# warps_v30.net
KiCad netlist of a schematic drawn in EAGLE
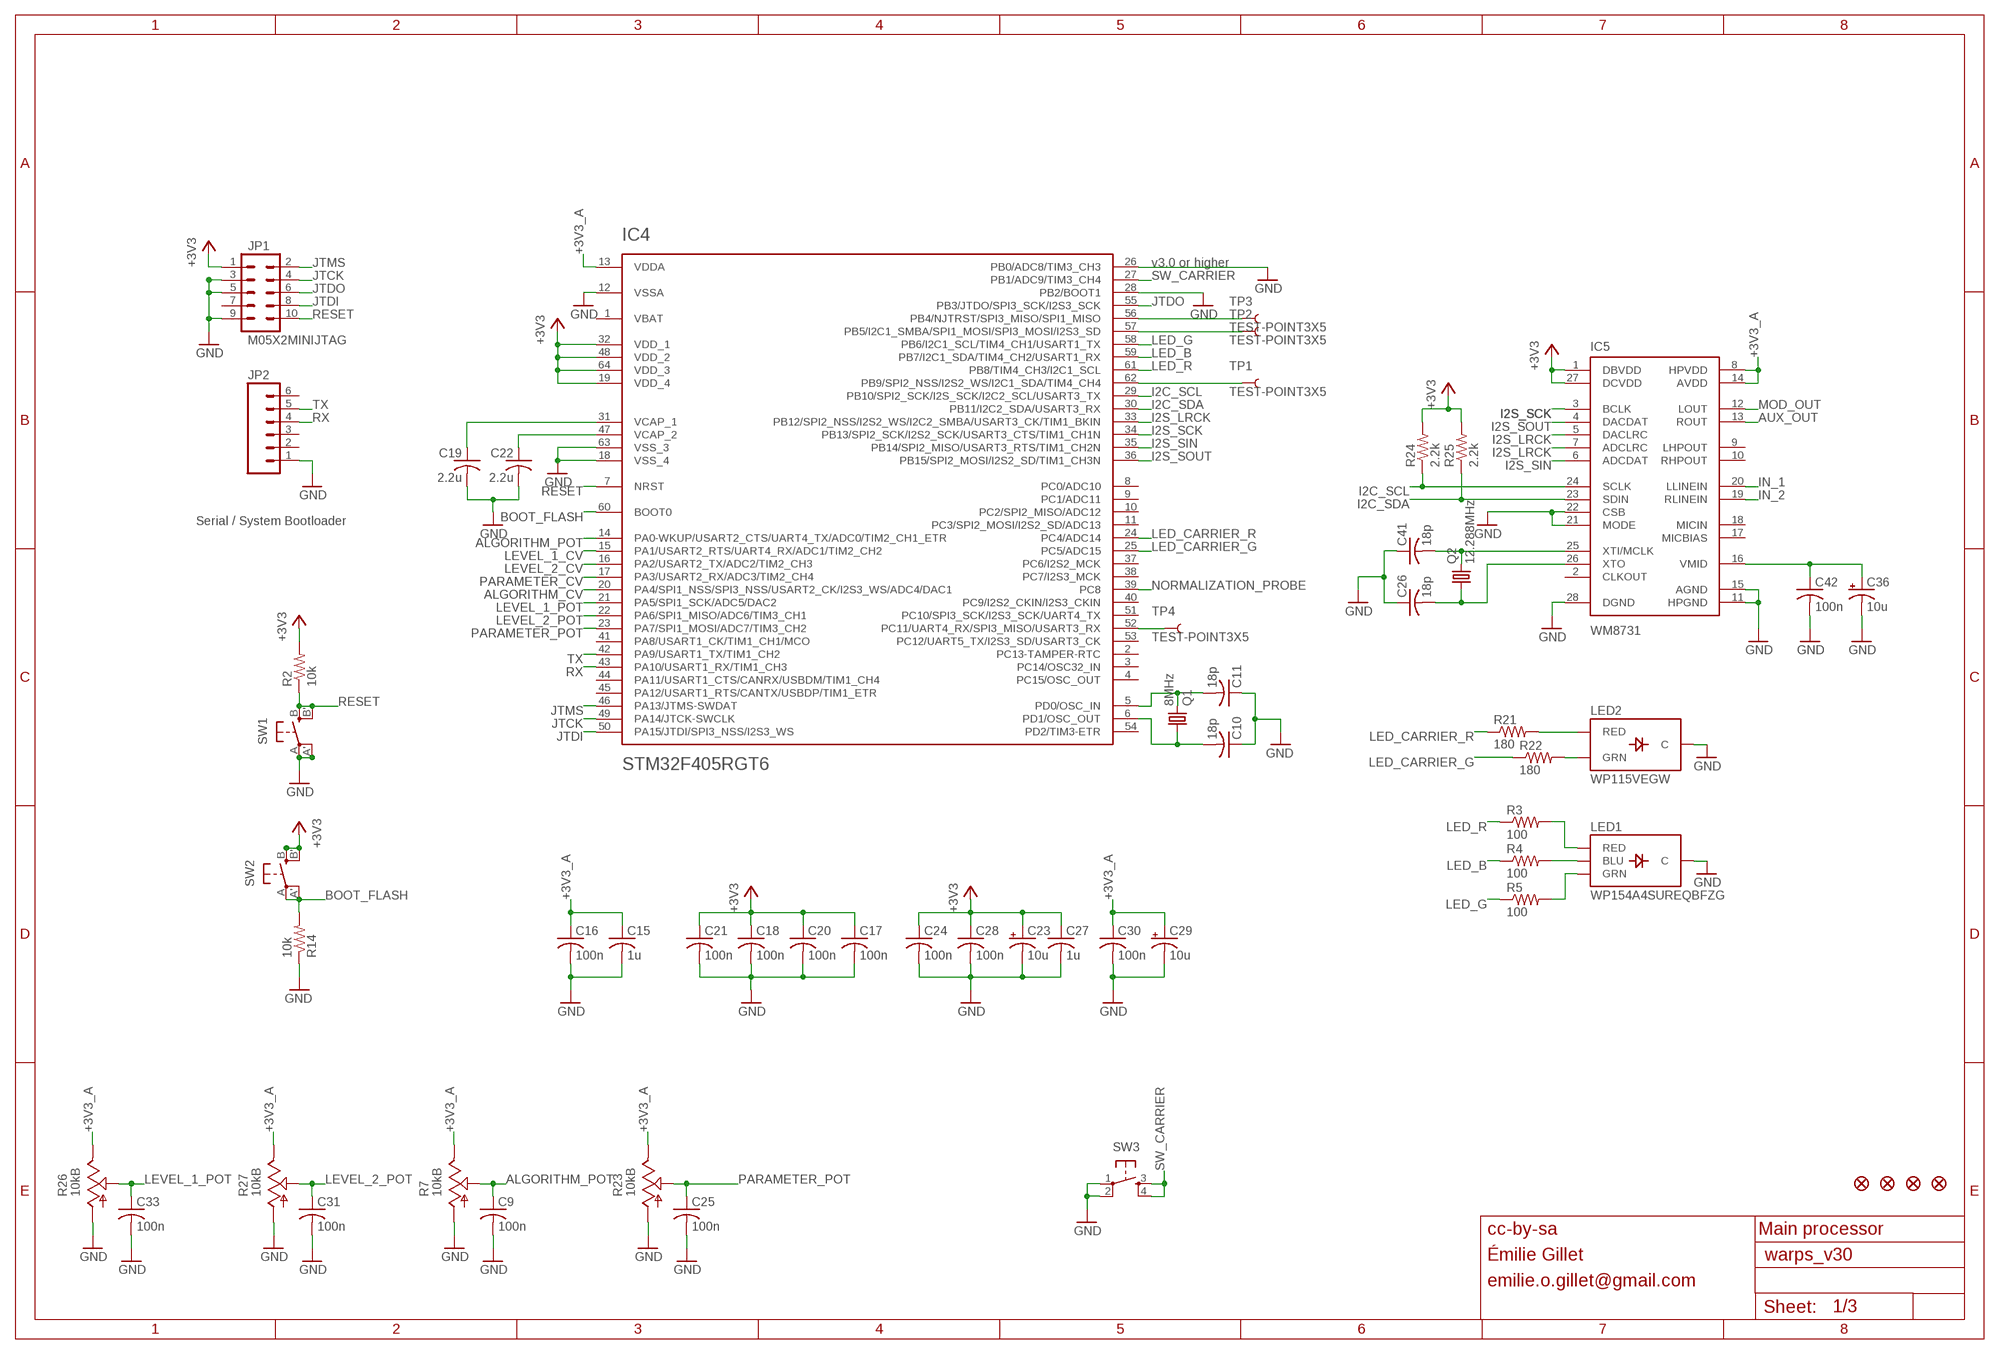
[diagram p0: schematic, sheet 1]
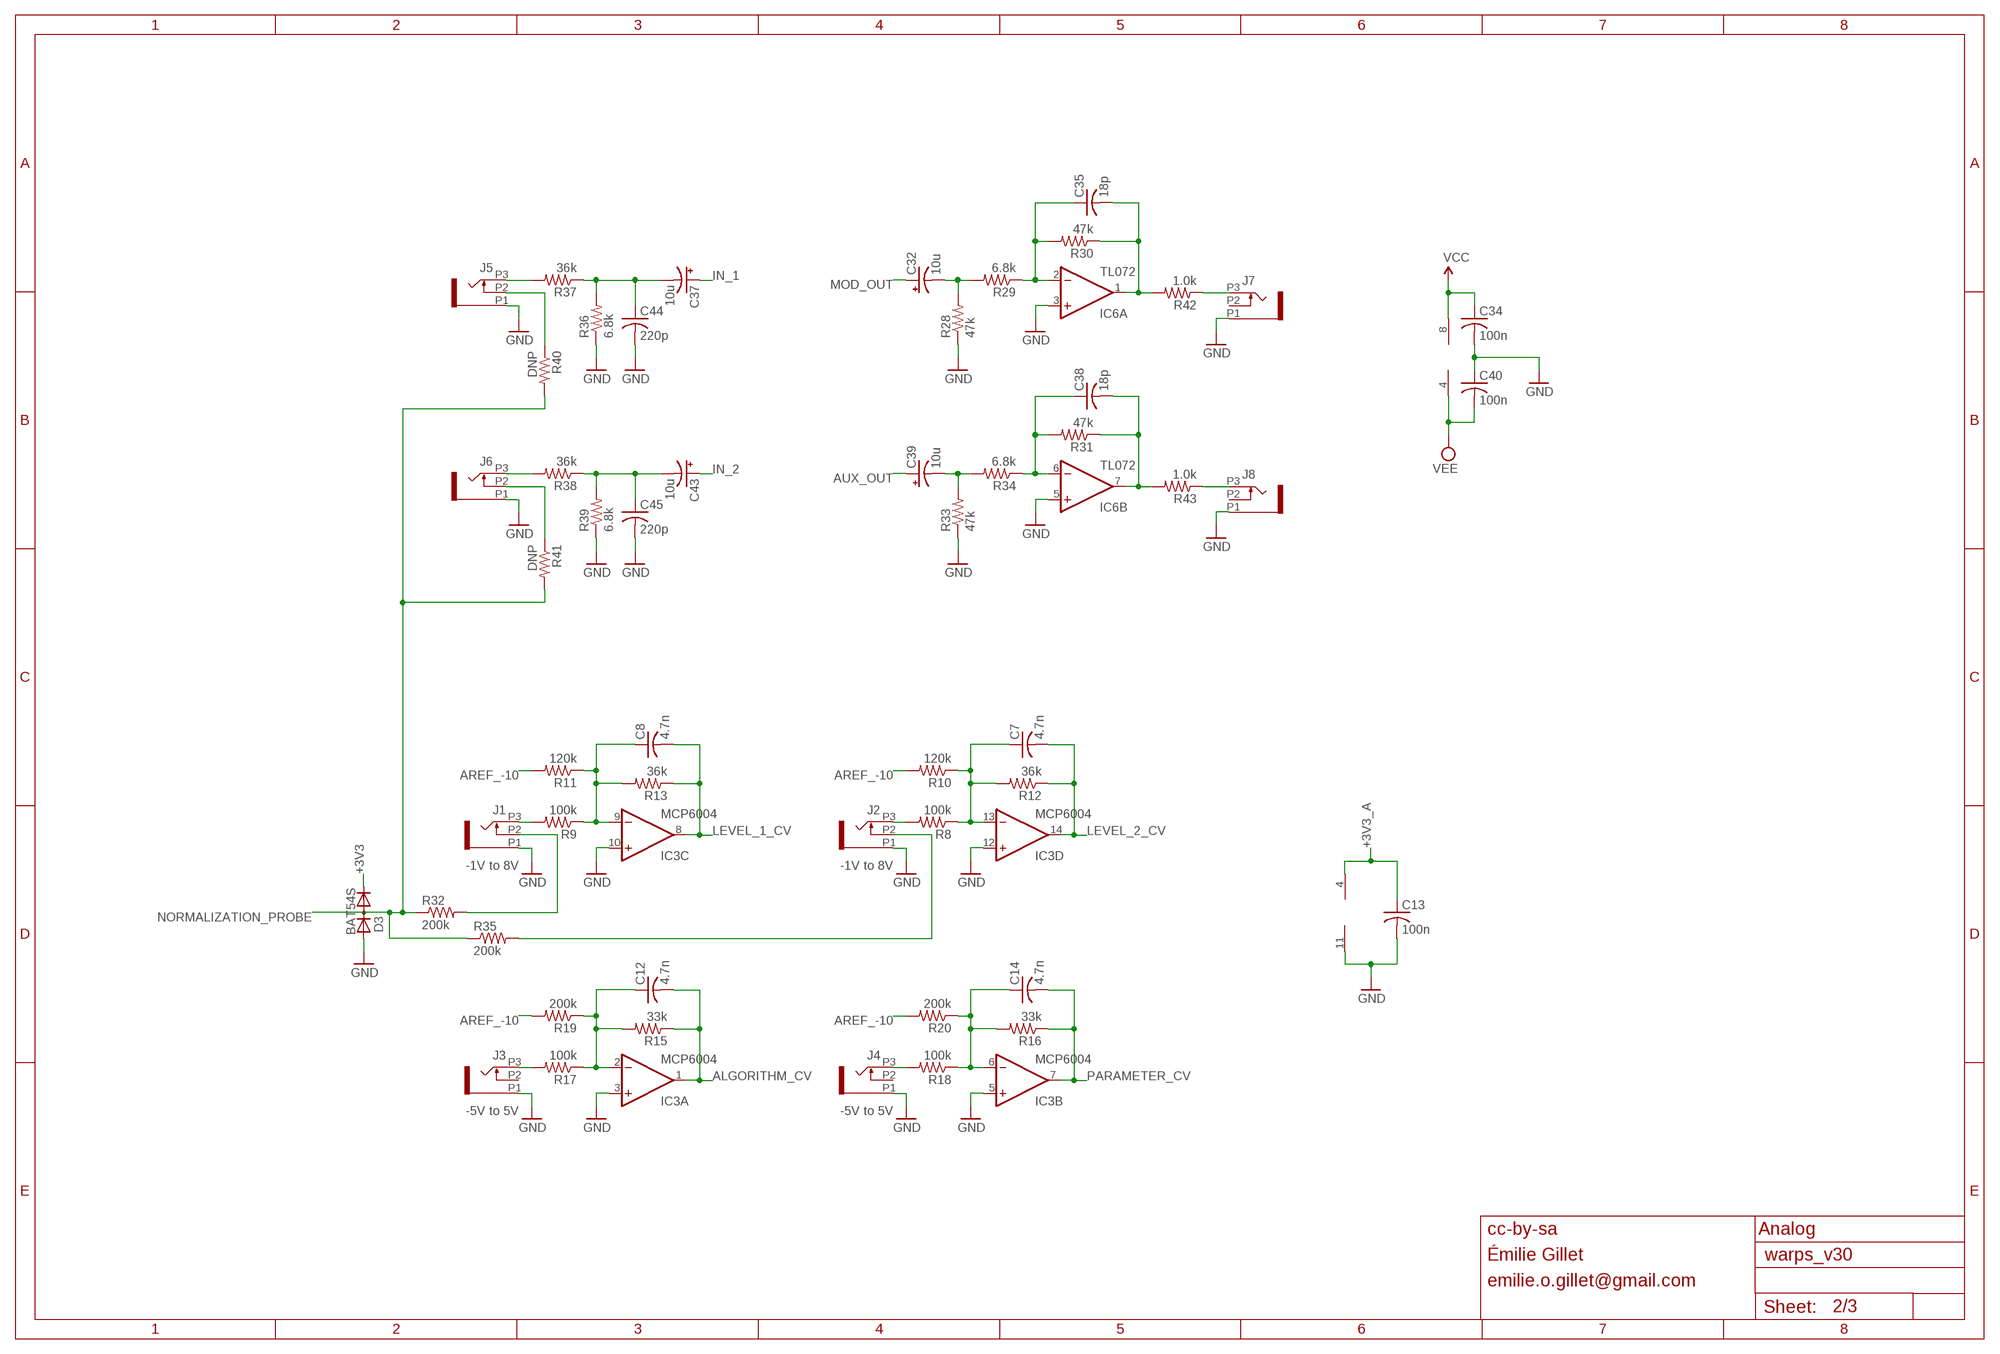
[diagram p1: schematic, sheet 2]
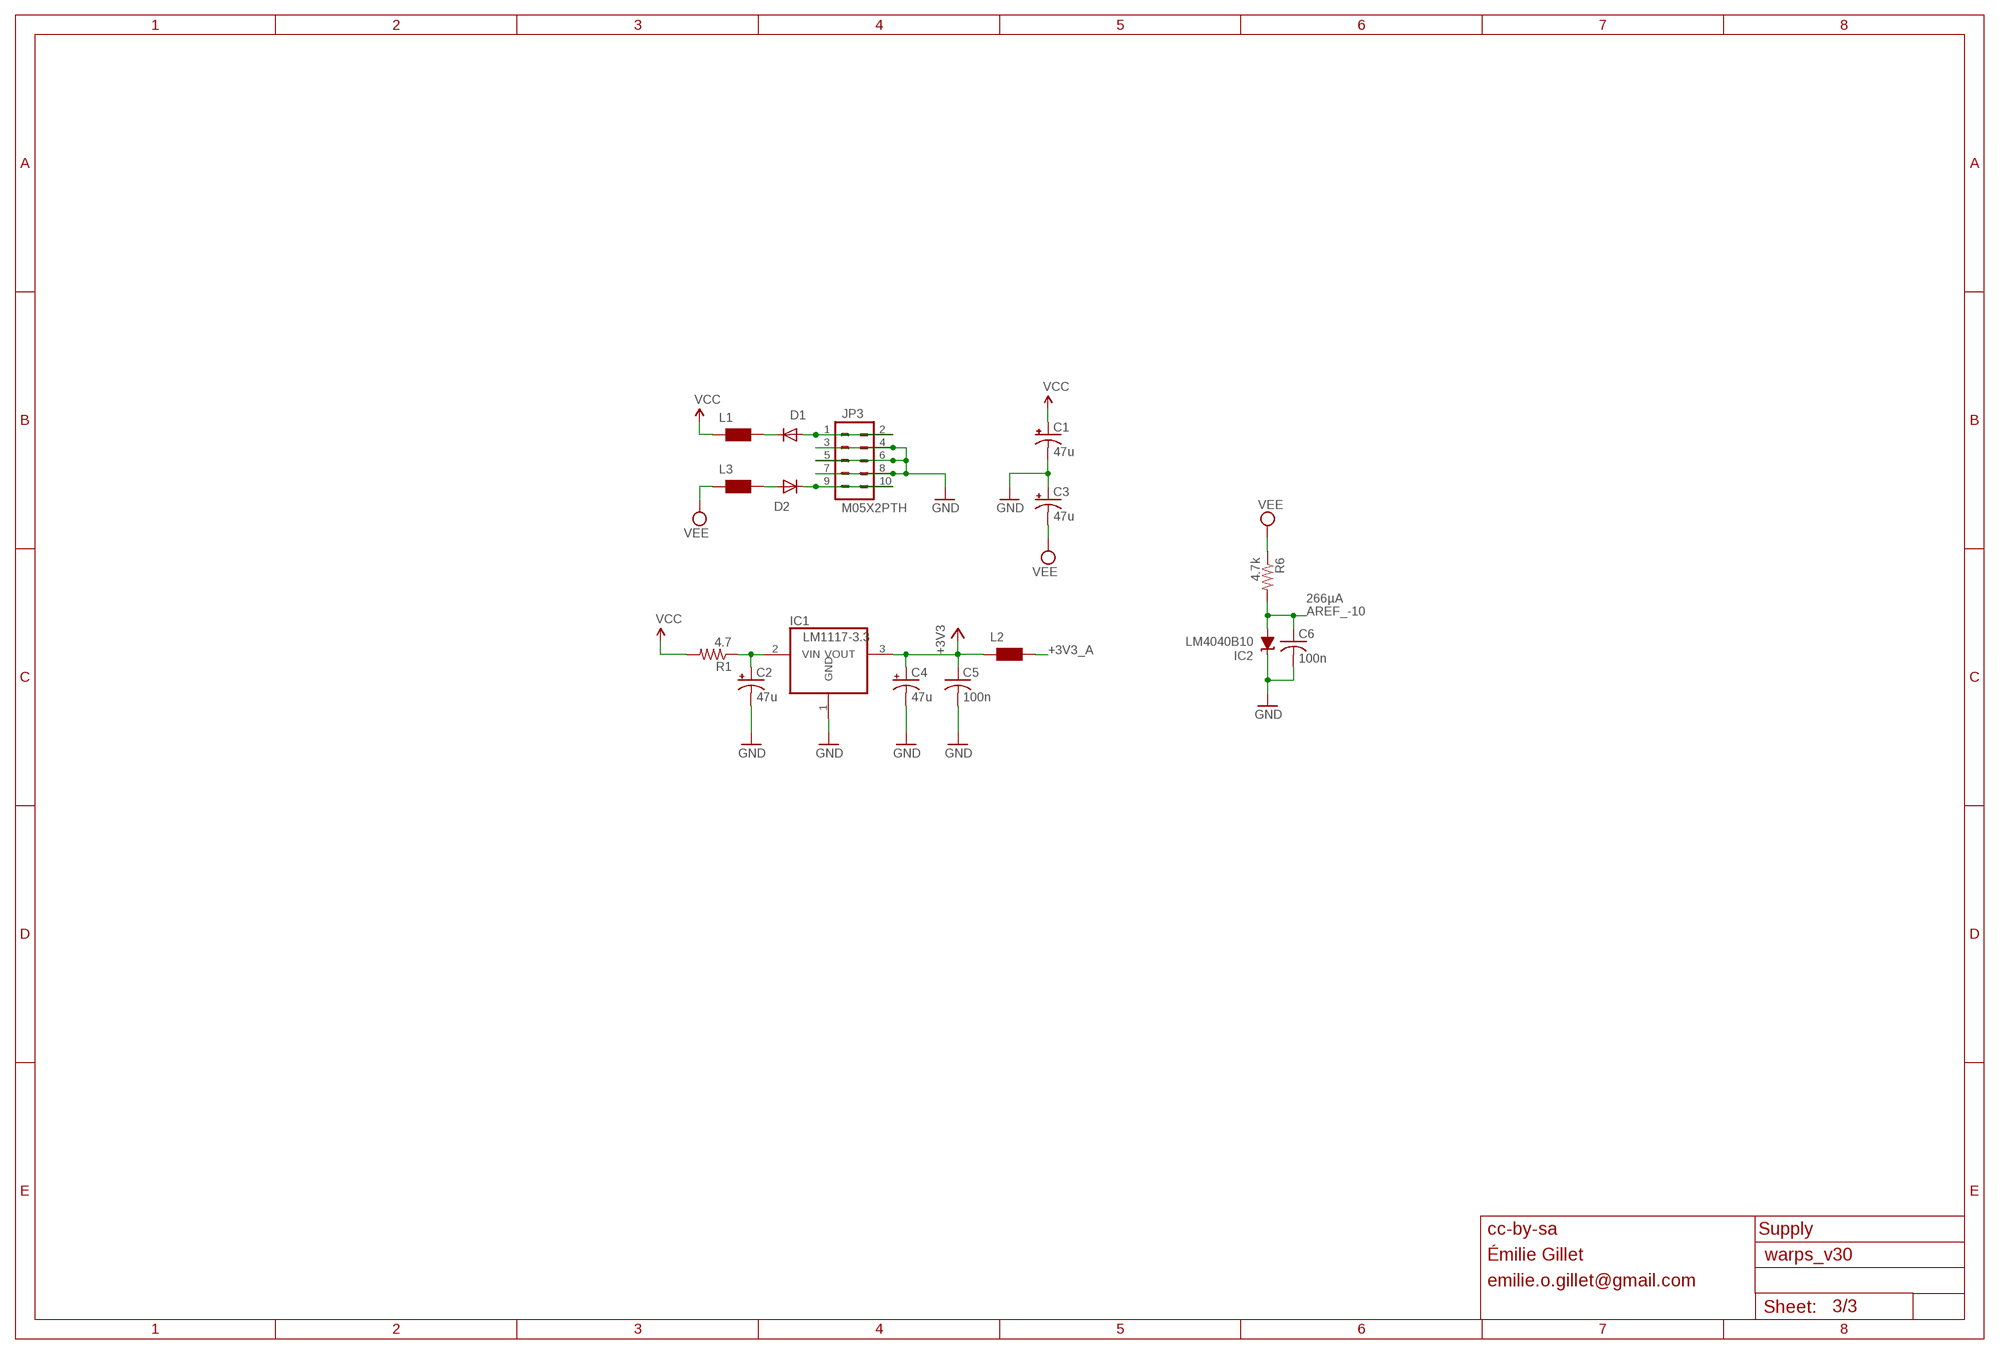
[diagram p2: schematic, sheet 3]

(export (version "E")
  (design (tool "Eeschema 10.0.6"))
  (components
    (comp (ref "C9")
      (value "100n")
      (footprint "eagle-import:C0603")
      (libsource (lib "eagle-import") (part "C-USC0603"))
    )
    (comp (ref "C10")
      (value "18p")
      (footprint "eagle-import:C0603")
      (libsource (lib "eagle-import") (part "C-USC0603"))
    )
    (comp (ref "C11")
      (value "18p")
      (footprint "eagle-import:C0603")
      (libsource (lib "eagle-import") (part "C-USC0603"))
    )
    (comp (ref "C15")
      (value "1u")
      (footprint "eagle-import:C0603")
      (libsource (lib "eagle-import") (part "C-USC0603"))
    )
    (comp (ref "C16")
      (value "100n")
      (footprint "eagle-import:C0603")
      (libsource (lib "eagle-import") (part "C-USC0603"))
    )
    (comp (ref "C17")
      (value "100n")
      (footprint "eagle-import:C0603")
      (libsource (lib "eagle-import") (part "C-USC0603"))
    )
    (comp (ref "C18")
      (value "100n")
      (footprint "eagle-import:C0603")
      (libsource (lib "eagle-import") (part "C-USC0603"))
    )
    (comp (ref "C19")
      (value "2.2u")
      (footprint "eagle-import:C0805")
      (libsource (lib "eagle-import") (part "C-USC0805"))
    )
    (comp (ref "C20")
      (value "100n")
      (footprint "eagle-import:C0603")
      (libsource (lib "eagle-import") (part "C-USC0603"))
    )
    (comp (ref "C21")
      (value "100n")
      (footprint "eagle-import:C0603")
      (libsource (lib "eagle-import") (part "C-USC0603"))
    )
    (comp (ref "C22")
      (value "2.2u")
      (footprint "eagle-import:C0805")
      (libsource (lib "eagle-import") (part "C-USC0805"))
    )
    (comp (ref "C23")
      (value "10u")
      (footprint "eagle-import:PANASONIC_A")
      (libsource (lib "eagle-import") (part "CPOL-USA"))
    )
    (comp (ref "C24")
      (value "100n")
      (footprint "eagle-import:C0603")
      (libsource (lib "eagle-import") (part "C-USC0603"))
    )
    (comp (ref "C25")
      (value "100n")
      (footprint "eagle-import:C0603")
      (libsource (lib "eagle-import") (part "C-USC0603"))
    )
    (comp (ref "C26")
      (value "18p")
      (footprint "eagle-import:C0603")
      (libsource (lib "eagle-import") (part "C-USC0603"))
    )
    (comp (ref "C27")
      (value "1u")
      (footprint "eagle-import:C0603")
      (libsource (lib "eagle-import") (part "C-USC0603"))
    )
    (comp (ref "C28")
      (value "100n")
      (footprint "eagle-import:C0603")
      (libsource (lib "eagle-import") (part "C-USC0603"))
    )
    (comp (ref "C29")
      (value "10u")
      (footprint "eagle-import:PANASONIC_A")
      (libsource (lib "eagle-import") (part "CPOL-USA"))
    )
    (comp (ref "C30")
      (value "100n")
      (footprint "eagle-import:C0603")
      (libsource (lib "eagle-import") (part "C-USC0603"))
    )
    (comp (ref "C31")
      (value "100n")
      (footprint "eagle-import:C0603")
      (libsource (lib "eagle-import") (part "C-USC0603"))
    )
    (comp (ref "C33")
      (value "100n")
      (footprint "eagle-import:C0603")
      (libsource (lib "eagle-import") (part "C-USC0603"))
    )
    (comp (ref "C36")
      (value "10u")
      (footprint "eagle-import:PANASONIC_A")
      (libsource (lib "eagle-import") (part "CPOL-USA"))
    )
    (comp (ref "C41")
      (value "18p")
      (footprint "eagle-import:C0603")
      (libsource (lib "eagle-import") (part "C-USC0603"))
    )
    (comp (ref "C42")
      (value "100n")
      (footprint "eagle-import:C0603")
      (libsource (lib "eagle-import") (part "C-USC0603"))
    )
    (comp (ref "F1")
      (value "FIDUCIAL1X2")
      (footprint "eagle-import:FIDUCIAL-1X2")
      (libsource (lib "eagle-import") (part "FIDUCIAL1X2"))
    )
    (comp (ref "F2")
      (value "FIDUCIAL1X2")
      (footprint "eagle-import:FIDUCIAL-1X2")
      (libsource (lib "eagle-import") (part "FIDUCIAL1X2"))
    )
    (comp (ref "F3")
      (value "FIDUCIAL1X2")
      (footprint "eagle-import:FIDUCIAL-1X2")
      (libsource (lib "eagle-import") (part "FIDUCIAL1X2"))
    )
    (comp (ref "F4")
      (value "FIDUCIAL1X2")
      (footprint "eagle-import:FIDUCIAL-1X2")
      (libsource (lib "eagle-import") (part "FIDUCIAL1X2"))
    )
    (comp (ref "IC4")
      (value "STM32F405RGT6")
      (footprint "eagle-import:TQFP-10X10-64")
      (libsource (lib "eagle-import") (part "STM32F20X"))
    )
    (comp (ref "IC5")
      (value "WM8731")
      (footprint "eagle-import:SSOP28")
      (libsource (lib "eagle-import") (part "WM8731"))
    )
    (comp (ref "JP1")
      (value "M05X2MINIJTAG")
      (footprint "eagle-import:2X5-1.27")
      (libsource (lib "eagle-import") (part "M05X2MINIJTAG"))
    )
    (comp (ref "JP2")
      (value "M06SIP")
      (footprint "eagle-import:1X06")
      (libsource (lib "eagle-import") (part "M06SIP"))
    )
    (comp (ref "LED1")
      (value "WP154A4SUREQBFZG")
      (footprint "eagle-import:LED-TRICOLOR-THROUGHHOLE")
      (libsource (lib "eagle-import") (part "LED-TRICOLOR-THROUGHHOLE"))
    )
    (comp (ref "LED2")
      (value "WP115VEGW")
      (footprint "eagle-import:LED-BICOLOR-THROUGHHOLE")
      (libsource (lib "eagle-import") (part "LED-BICOLOR-THROUGHHOLE"))
    )
    (comp (ref "Q1")
      (value "8MHz")
      (footprint "eagle-import:HC49UP")
      (libsource (lib "eagle-import") (part "CRYSTALHC49UP"))
    )
    (comp (ref "Q2")
      (value "12.288MHz")
      (footprint "eagle-import:HC49UP")
      (libsource (lib "eagle-import") (part "CRYSTALHC49UP"))
    )
    (comp (ref "R2")
      (value "10k")
      (footprint "eagle-import:R0603")
      (libsource (lib "eagle-import") (part "R-US_R0603"))
    )
    (comp (ref "R3")
      (value "100")
      (footprint "eagle-import:R0603")
      (libsource (lib "eagle-import") (part "R-US_R0603"))
    )
    (comp (ref "R4")
      (value "100")
      (footprint "eagle-import:R0603")
      (libsource (lib "eagle-import") (part "R-US_R0603"))
    )
    (comp (ref "R5")
      (value "100")
      (footprint "eagle-import:R0603")
      (libsource (lib "eagle-import") (part "R-US_R0603"))
    )
    (comp (ref "R7")
      (value "10kB")
      (footprint "eagle-import:ALPS_POT_VERTICAL_PS")
      (libsource (lib "eagle-import") (part "POT_USVERTICAL_PS"))
    )
    (comp (ref "R14")
      (value "10k")
      (footprint "eagle-import:R0603")
      (libsource (lib "eagle-import") (part "R-US_R0603"))
    )
    (comp (ref "R21")
      (value "180")
      (footprint "eagle-import:R0603")
      (libsource (lib "eagle-import") (part "R-US_R0603"))
    )
    (comp (ref "R22")
      (value "180")
      (footprint "eagle-import:R0603")
      (libsource (lib "eagle-import") (part "R-US_R0603"))
    )
    (comp (ref "R23")
      (value "10kB")
      (footprint "eagle-import:ALPS_POT_VERTICAL_PS")
      (libsource (lib "eagle-import") (part "POT_USVERTICAL_PS"))
    )
    (comp (ref "R24")
      (value "2.2k")
      (footprint "eagle-import:R0603")
      (libsource (lib "eagle-import") (part "R-US_R0603"))
    )
    (comp (ref "R25")
      (value "2.2k")
      (footprint "eagle-import:R0603")
      (libsource (lib "eagle-import") (part "R-US_R0603"))
    )
    (comp (ref "R26")
      (value "10kB")
      (footprint "eagle-import:ALPS_POT_VERTICAL")
      (libsource (lib "eagle-import") (part "POT_USVERTICAL"))
    )
    (comp (ref "R27")
      (value "10kB")
      (footprint "eagle-import:ALPS_POT_VERTICAL")
      (libsource (lib "eagle-import") (part "POT_USVERTICAL"))
    )
    (comp (ref "SW1")
      (value "EVQQ2")
      (footprint "eagle-import:EVQ-Q2")
      (libsource (lib "eagle-import") (part "EVQQ2"))
    )
    (comp (ref "SW2")
      (value "EVQQ2")
      (footprint "eagle-import:EVQ-Q2")
      (libsource (lib "eagle-import") (part "EVQQ2"))
    )
    (comp (ref "SW3")
      (value "TAC_SWITCHPTH")
      (footprint "eagle-import:TACTILE-PTH")
      (libsource (lib "eagle-import") (part "TAC_SWITCHPTH"))
    )
    (comp (ref "TP1")
      (value "TEST-POINT3X5")
      (footprint "eagle-import:PAD.03X.05")
      (libsource (lib "eagle-import") (part "TEST-POINT3X5"))
    )
    (comp (ref "TP2")
      (value "TEST-POINT3X5")
      (footprint "eagle-import:PAD.03X.05")
      (libsource (lib "eagle-import") (part "TEST-POINT3X5"))
    )
    (comp (ref "TP3")
      (value "TEST-POINT3X5")
      (footprint "eagle-import:PAD.03X.05")
      (libsource (lib "eagle-import") (part "TEST-POINT3X5"))
    )
    (comp (ref "TP4")
      (value "TEST-POINT3X5")
      (footprint "eagle-import:PAD.03X.05")
      (libsource (lib "eagle-import") (part "TEST-POINT3X5"))
    )
    (comp (ref "C1")
      (value "47u")
      (footprint "eagle-import:PANASONIC_D")
      (libsource (lib "eagle-import") (part "CPOL-USD"))
    )
    (comp (ref "C2")
      (value "47u")
      (footprint "eagle-import:PANASONIC_D")
      (libsource (lib "eagle-import") (part "CPOL-USD"))
    )
    (comp (ref "C3")
      (value "47u")
      (footprint "eagle-import:PANASONIC_D")
      (libsource (lib "eagle-import") (part "CPOL-USD"))
    )
    (comp (ref "C4")
      (value "47u")
      (footprint "eagle-import:PANASONIC_D")
      (libsource (lib "eagle-import") (part "CPOL-USD"))
    )
    (comp (ref "C5")
      (value "100n")
      (footprint "eagle-import:C0603")
      (libsource (lib "eagle-import") (part "C-USC0603"))
    )
    (comp (ref "C6")
      (value "100n")
      (footprint "eagle-import:C0603")
      (libsource (lib "eagle-import") (part "C-USC0603"))
    )
    (comp (ref "D1")
      (value "1N5819HW")
      (footprint "eagle-import:SOD123")
      (libsource (lib "eagle-import") (part "DIODE-SOD123"))
    )
    (comp (ref "D2")
      (value "1N5819HW")
      (footprint "eagle-import:SOD123")
      (libsource (lib "eagle-import") (part "DIODE-SOD123"))
    )
    (comp (ref "IC1")
      (value "LM1117-3.3")
      (footprint "eagle-import:TO252")
      (libsource (lib "eagle-import") (part "REG1117T"))
    )
    (comp (ref "IC2")
      (value "LM4040B10")
      (footprint "eagle-import:DBZ_R-PDSO-G3")
      (libsource (lib "eagle-import") (part "LM4041DBZB12"))
    )
    (comp (ref "JP3")
      (value "M05X2PTH")
      (footprint "eagle-import:AVR_ICSP")
      (libsource (lib "eagle-import") (part "M05X2PTH"))
    )
    (comp (ref "L1")
      (value "WE-CBF_0603")
      (footprint "eagle-import:0603")
      (libsource (lib "eagle-import") (part "WE-CBF_0603"))
    )
    (comp (ref "L2")
      (value "WE-CBF_0603")
      (footprint "eagle-import:0603")
      (libsource (lib "eagle-import") (part "WE-CBF_0603"))
    )
    (comp (ref "L3")
      (value "WE-CBF_0603")
      (footprint "eagle-import:0603")
      (libsource (lib "eagle-import") (part "WE-CBF_0603"))
    )
    (comp (ref "R1")
      (value "4.7")
      (footprint "eagle-import:R1206")
      (libsource (lib "eagle-import") (part "R-US_R1206"))
    )
    (comp (ref "R6")
      (value "4.7k")
      (footprint "eagle-import:R0603")
      (libsource (lib "eagle-import") (part "R-US_R0603"))
    )
    (comp (ref "C7")
      (value "4.7n")
      (footprint "eagle-import:C0603")
      (libsource (lib "eagle-import") (part "C-USC0603"))
    )
    (comp (ref "C8")
      (value "4.7n")
      (footprint "eagle-import:C0603")
      (libsource (lib "eagle-import") (part "C-USC0603"))
    )
    (comp (ref "C12")
      (value "4.7n")
      (footprint "eagle-import:C0603")
      (libsource (lib "eagle-import") (part "C-USC0603"))
    )
    (comp (ref "C13")
      (value "100n")
      (footprint "eagle-import:C0603")
      (libsource (lib "eagle-import") (part "C-USC0603"))
    )
    (comp (ref "C14")
      (value "4.7n")
      (footprint "eagle-import:C0603")
      (libsource (lib "eagle-import") (part "C-USC0603"))
    )
    (comp (ref "C32")
      (value "10u")
      (footprint "eagle-import:PANASONIC_A")
      (libsource (lib "eagle-import") (part "CPOL-USA"))
    )
    (comp (ref "C34")
      (value "100n")
      (footprint "eagle-import:C0603")
      (libsource (lib "eagle-import") (part "C-USC0603"))
    )
    (comp (ref "C35")
      (value "18p")
      (footprint "eagle-import:C0603")
      (libsource (lib "eagle-import") (part "C-USC0603"))
    )
    (comp (ref "C37")
      (value "10u")
      (footprint "eagle-import:PANASONIC_A")
      (libsource (lib "eagle-import") (part "CPOL-USA"))
    )
    (comp (ref "C38")
      (value "18p")
      (footprint "eagle-import:C0603")
      (libsource (lib "eagle-import") (part "C-USC0603"))
    )
    (comp (ref "C39")
      (value "10u")
      (footprint "eagle-import:PANASONIC_A")
      (libsource (lib "eagle-import") (part "CPOL-USA"))
    )
    (comp (ref "C40")
      (value "100n")
      (footprint "eagle-import:C0603")
      (libsource (lib "eagle-import") (part "C-USC0603"))
    )
    (comp (ref "C43")
      (value "10u")
      (footprint "eagle-import:PANASONIC_A")
      (libsource (lib "eagle-import") (part "CPOL-USA"))
    )
    (comp (ref "C44")
      (value "220p")
      (footprint "eagle-import:C0603")
      (libsource (lib "eagle-import") (part "C-USC0603"))
    )
    (comp (ref "C45")
      (value "220p")
      (footprint "eagle-import:C0603")
      (libsource (lib "eagle-import") (part "C-USC0603"))
    )
    (comp (ref "D3")
      (value "BAT54S")
      (footprint "eagle-import:SOT23")
      (libsource (lib "eagle-import") (part "DIODE_2CACA-SOT23"))
    )
    (comp (ref "IC3")
      (value "MCP6004")
      (footprint "eagle-import:SO14")
      (libsource (lib "eagle-import") (part "TL074D"))
    )
    (comp (ref "IC6")
      (value "TL072")
      (footprint "eagle-import:SO08")
      (libsource (lib "eagle-import") (part "TL072D"))
    )
    (comp (ref "J1")
      (value "PJ301_THONKICONN6")
      (footprint "eagle-import:WQP_PJ_301M6")
      (libsource (lib "eagle-import") (part "PJ301_THONKICONN6"))
    )
    (comp (ref "J2")
      (value "PJ301_THONKICONN6")
      (footprint "eagle-import:WQP_PJ_301M6")
      (libsource (lib "eagle-import") (part "PJ301_THONKICONN6"))
    )
    (comp (ref "J3")
      (value "PJ301_THONKICONN6")
      (footprint "eagle-import:WQP_PJ_301M6")
      (libsource (lib "eagle-import") (part "PJ301_THONKICONN6"))
    )
    (comp (ref "J4")
      (value "PJ301_THONKICONN6")
      (footprint "eagle-import:WQP_PJ_301M6")
      (libsource (lib "eagle-import") (part "PJ301_THONKICONN6"))
    )
    (comp (ref "J5")
      (value "PJ301_THONKICONN6")
      (footprint "eagle-import:WQP_PJ_301M6")
      (libsource (lib "eagle-import") (part "PJ301_THONKICONN6"))
    )
    (comp (ref "J6")
      (value "PJ301_THONKICONN6")
      (footprint "eagle-import:WQP_PJ_301M6")
      (libsource (lib "eagle-import") (part "PJ301_THONKICONN6"))
    )
    (comp (ref "J7")
      (value "PJ301_THONKICONN6")
      (footprint "eagle-import:WQP_PJ_301M6")
      (libsource (lib "eagle-import") (part "PJ301_THONKICONN6"))
    )
    (comp (ref "J8")
      (value "PJ301_THONKICONN6")
      (footprint "eagle-import:WQP_PJ_301M6")
      (libsource (lib "eagle-import") (part "PJ301_THONKICONN6"))
    )
    (comp (ref "R8")
      (value "100k")
      (footprint "eagle-import:R0603")
      (libsource (lib "eagle-import") (part "R-US_R0603"))
    )
    (comp (ref "R9")
      (value "100k")
      (footprint "eagle-import:R0603")
      (libsource (lib "eagle-import") (part "R-US_R0603"))
    )
    (comp (ref "R10")
      (value "120k")
      (footprint "eagle-import:R0603")
      (libsource (lib "eagle-import") (part "R-US_R0603"))
    )
    (comp (ref "R11")
      (value "120k")
      (footprint "eagle-import:R0603")
      (libsource (lib "eagle-import") (part "R-US_R0603"))
    )
    (comp (ref "R12")
      (value "36k")
      (footprint "eagle-import:R0603")
      (libsource (lib "eagle-import") (part "R-US_R0603"))
    )
    (comp (ref "R13")
      (value "36k")
      (footprint "eagle-import:R0603")
      (libsource (lib "eagle-import") (part "R-US_R0603"))
    )
    (comp (ref "R15")
      (value "33k")
      (footprint "eagle-import:R0603")
      (libsource (lib "eagle-import") (part "R-US_R0603"))
    )
    (comp (ref "R16")
      (value "33k")
      (footprint "eagle-import:R0603")
      (libsource (lib "eagle-import") (part "R-US_R0603"))
    )
    (comp (ref "R17")
      (value "100k")
      (footprint "eagle-import:R0603")
      (libsource (lib "eagle-import") (part "R-US_R0603"))
    )
    (comp (ref "R18")
      (value "100k")
      (footprint "eagle-import:R0603")
      (libsource (lib "eagle-import") (part "R-US_R0603"))
    )
    (comp (ref "R19")
      (value "200k")
      (footprint "eagle-import:R0603")
      (libsource (lib "eagle-import") (part "R-US_R0603"))
    )
    (comp (ref "R20")
      (value "200k")
      (footprint "eagle-import:R0603")
      (libsource (lib "eagle-import") (part "R-US_R0603"))
    )
    (comp (ref "R28")
      (value "47k")
      (footprint "eagle-import:R0603")
      (libsource (lib "eagle-import") (part "R-US_R0603"))
    )
    (comp (ref "R29")
      (value "6.8k")
      (footprint "eagle-import:R0603")
      (libsource (lib "eagle-import") (part "R-US_R0603"))
    )
    (comp (ref "R30")
      (value "47k")
      (footprint "eagle-import:R0603")
      (libsource (lib "eagle-import") (part "R-US_R0603"))
    )
    (comp (ref "R31")
      (value "47k")
      (footprint "eagle-import:R0603")
      (libsource (lib "eagle-import") (part "R-US_R0603"))
    )
    (comp (ref "R32")
      (value "200k")
      (footprint "eagle-import:R0603")
      (libsource (lib "eagle-import") (part "R-US_R0603"))
    )
    (comp (ref "R33")
      (value "47k")
      (footprint "eagle-import:R0603")
      (libsource (lib "eagle-import") (part "R-US_R0603"))
    )
    (comp (ref "R34")
      (value "6.8k")
      (footprint "eagle-import:R0603")
      (libsource (lib "eagle-import") (part "R-US_R0603"))
    )
    (comp (ref "R35")
      (value "200k")
      (footprint "eagle-import:R0603")
      (libsource (lib "eagle-import") (part "R-US_R0603"))
    )
    (comp (ref "R36")
      (value "6.8k")
      (footprint "eagle-import:R0603")
      (libsource (lib "eagle-import") (part "R-US_R0603"))
    )
    (comp (ref "R37")
      (value "36k")
      (footprint "eagle-import:R0603")
      (libsource (lib "eagle-import") (part "R-US_R0603"))
    )
    (comp (ref "R38")
      (value "36k")
      (footprint "eagle-import:R0603")
      (libsource (lib "eagle-import") (part "R-US_R0603"))
    )
    (comp (ref "R39")
      (value "6.8k")
      (footprint "eagle-import:R0603")
      (libsource (lib "eagle-import") (part "R-US_R0603"))
    )
    (comp (ref "R40")
      (value "DNP")
      (footprint "eagle-import:R0603")
      (libsource (lib "eagle-import") (part "R-US_R0603"))
    )
    (comp (ref "R41")
      (value "DNP")
      (footprint "eagle-import:R0603")
      (libsource (lib "eagle-import") (part "R-US_R0603"))
    )
    (comp (ref "R42")
      (value "1.0k")
      (footprint "eagle-import:R0603")
      (libsource (lib "eagle-import") (part "R-US_R0603"))
    )
    (comp (ref "R43")
      (value "1.0k")
      (footprint "eagle-import:R0603")
      (libsource (lib "eagle-import") (part "R-US_R0603"))
    )
  )
  (nets
    (net (code "1") (name "+3V3") (class "Default")
      (node (ref "C17") (pin "1") (pinfunction "1_1") (pintype "passive"))
      (node (ref "C18") (pin "1") (pinfunction "1_1") (pintype "passive"))
      (node (ref "C20") (pin "1") (pinfunction "1_1") (pintype "passive"))
      (node (ref "C21") (pin "1") (pinfunction "1_1") (pintype "passive"))
      (node (ref "C23") (pin "+") (pinfunction "+_+") (pintype "passive"))
      (node (ref "C24") (pin "1") (pinfunction "1_1") (pintype "passive"))
      (node (ref "C27") (pin "1") (pinfunction "1_1") (pintype "passive"))
      (node (ref "C28") (pin "1") (pinfunction "1_1") (pintype "passive"))
      (node (ref "C4") (pin "+") (pinfunction "+_+") (pintype "passive"))
      (node (ref "C5") (pin "1") (pinfunction "1_1") (pintype "passive"))
      (node (ref "D3") (pin "2") (pinfunction "C_2") (pintype "passive"))
      (node (ref "IC1") (pin "3") (pinfunction "VOUT_3") (pintype "output"))
      (node (ref "IC4") (pin "19") (pinfunction "VDD_4_19") (pintype "power_in"))
      (node (ref "IC4") (pin "32") (pinfunction "VDD_1_32") (pintype "power_in"))
      (node (ref "IC4") (pin "48") (pinfunction "VDD_2_48") (pintype "power_in"))
      (node (ref "IC4") (pin "64") (pinfunction "VDD_3_64") (pintype "power_in"))
      (node (ref "IC5") (pin "1") (pinfunction "DBVDD_1") (pintype "bidirectional"))
      (node (ref "IC5") (pin "27") (pinfunction "DCVDD_27") (pintype "bidirectional"))
      (node (ref "JP1") (pin "1") (pinfunction "1_1") (pintype "passive"))
      (node (ref "L2") (pin "1") (pinfunction "1_1") (pintype "passive"))
      (node (ref "R2") (pin "2") (pinfunction "2_2") (pintype "passive"))
      (node (ref "R24") (pin "2") (pinfunction "2_2") (pintype "passive"))
      (node (ref "R25") (pin "2") (pinfunction "2_2") (pintype "passive"))
      (node (ref "SW2") (pin "B") (pinfunction "S_B") (pintype "passive"))
      (node (ref "SW2") (pin "B'") (pinfunction "S1_B'") (pintype "passive"))
    )
    (net (code "2") (name "+3V3_A") (class "Default")
      (node (ref "C13") (pin "1") (pinfunction "1_1") (pintype "passive"))
      (node (ref "C15") (pin "1") (pinfunction "1_1") (pintype "passive"))
      (node (ref "C16") (pin "1") (pinfunction "1_1") (pintype "passive"))
      (node (ref "C29") (pin "+") (pinfunction "+_+") (pintype "passive"))
      (node (ref "C30") (pin "1") (pinfunction "1_1") (pintype "passive"))
      (node (ref "IC3") (pin "4") (pinfunction "V+_4") (pintype "power_in"))
      (node (ref "IC4") (pin "13") (pinfunction "VDDA_13") (pintype "power_in"))
      (node (ref "IC5") (pin "14") (pinfunction "AVDD_14") (pintype "bidirectional"))
      (node (ref "IC5") (pin "8") (pinfunction "HPVDD_8") (pintype "bidirectional"))
      (node (ref "L2") (pin "2") (pinfunction "2_2") (pintype "passive"))
      (node (ref "R23") (pin "P$1") (pinfunction "E_P$1") (pintype "passive"))
      (node (ref "R26") (pin "P$1") (pinfunction "E_P$1") (pintype "passive"))
      (node (ref "R27") (pin "P$1") (pinfunction "E_P$1") (pintype "passive"))
      (node (ref "R7") (pin "P$1") (pinfunction "E_P$1") (pintype "passive"))
    )
    (net (code "3") (name "ALGORITHM_CV") (class "Default")
      (node (ref "C12") (pin "2") (pinfunction "2_2") (pintype "passive"))
      (node (ref "IC3") (pin "1") (pinfunction "OUT_1") (pintype "output"))
      (node (ref "IC4") (pin "20") (pinfunction "PA4/SPI1_NSS/SPI3_NSS/USART2_CK/I2S3_WS/ADC4/DAC1_20") (pintype "bidirectional"))
      (node (ref "R15") (pin "1") (pinfunction "1_1") (pintype "passive"))
    )
    (net (code "4") (name "ALGORITHM_POT") (class "Default")
      (node (ref "C9") (pin "1") (pinfunction "1_1") (pintype "passive"))
      (node (ref "IC4") (pin "14") (pinfunction "PA0-WKUP/USART2_CTS/UART4_TX/ADC0/TIM2_CH1_ETR_14") (pintype "bidirectional"))
      (node (ref "R7") (pin "P$2") (pinfunction "S_P$2") (pintype "passive"))
    )
    (net (code "5") (name "AREF_-10") (class "Default")
      (node (ref "C6") (pin "1") (pinfunction "1_1") (pintype "passive"))
      (node (ref "IC2") (pin "2") (pinfunction "A_2") (pintype "passive"))
      (node (ref "R10") (pin "2") (pinfunction "2_2") (pintype "passive"))
      (node (ref "R11") (pin "2") (pinfunction "2_2") (pintype "passive"))
      (node (ref "R19") (pin "2") (pinfunction "2_2") (pintype "passive"))
      (node (ref "R20") (pin "2") (pinfunction "2_2") (pintype "passive"))
      (node (ref "R6") (pin "2") (pinfunction "2_2") (pintype "passive"))
    )
    (net (code "6") (name "AUX_OUT") (class "Default")
      (node (ref "C39") (pin "+") (pinfunction "+_+") (pintype "passive"))
      (node (ref "IC5") (pin "13") (pinfunction "ROUT_13") (pintype "bidirectional"))
    )
    (net (code "7") (name "BOOT_FLASH") (class "Default")
      (node (ref "IC4") (pin "60") (pinfunction "BOOT0_60") (pintype "bidirectional"))
      (node (ref "R14") (pin "2") (pinfunction "2_2") (pintype "passive"))
      (node (ref "SW2") (pin "A") (pinfunction "P_A") (pintype "passive"))
      (node (ref "SW2") (pin "A'") (pinfunction "P1_A'") (pintype "passive"))
    )
    (net (code "8") (name "GND") (class "Default")
      (node (ref "C1") (pin "-") (pinfunction "-_-") (pintype "passive"))
      (node (ref "C10") (pin "1") (pinfunction "1_1") (pintype "passive"))
      (node (ref "C11") (pin "1") (pinfunction "1_1") (pintype "passive"))
      (node (ref "C13") (pin "2") (pinfunction "2_2") (pintype "passive"))
      (node (ref "C15") (pin "2") (pinfunction "2_2") (pintype "passive"))
      (node (ref "C16") (pin "2") (pinfunction "2_2") (pintype "passive"))
      (node (ref "C17") (pin "2") (pinfunction "2_2") (pintype "passive"))
      (node (ref "C18") (pin "2") (pinfunction "2_2") (pintype "passive"))
      (node (ref "C19") (pin "2") (pinfunction "2_2") (pintype "passive"))
      (node (ref "C2") (pin "-") (pinfunction "-_-") (pintype "passive"))
      (node (ref "C20") (pin "2") (pinfunction "2_2") (pintype "passive"))
      (node (ref "C21") (pin "2") (pinfunction "2_2") (pintype "passive"))
      (node (ref "C22") (pin "2") (pinfunction "2_2") (pintype "passive"))
      (node (ref "C23") (pin "-") (pinfunction "-_-") (pintype "passive"))
      (node (ref "C24") (pin "2") (pinfunction "2_2") (pintype "passive"))
      (node (ref "C25") (pin "2") (pinfunction "2_2") (pintype "passive"))
      (node (ref "C26") (pin "1") (pinfunction "1_1") (pintype "passive"))
      (node (ref "C27") (pin "2") (pinfunction "2_2") (pintype "passive"))
      (node (ref "C28") (pin "2") (pinfunction "2_2") (pintype "passive"))
      (node (ref "C29") (pin "-") (pinfunction "-_-") (pintype "passive"))
      (node (ref "C3") (pin "+") (pinfunction "+_+") (pintype "passive"))
      (node (ref "C30") (pin "2") (pinfunction "2_2") (pintype "passive"))
      (node (ref "C31") (pin "2") (pinfunction "2_2") (pintype "passive"))
      (node (ref "C33") (pin "2") (pinfunction "2_2") (pintype "passive"))
      (node (ref "C34") (pin "2") (pinfunction "2_2") (pintype "passive"))
      (node (ref "C36") (pin "-") (pinfunction "-_-") (pintype "passive"))
      (node (ref "C4") (pin "-") (pinfunction "-_-") (pintype "passive"))
      (node (ref "C40") (pin "1") (pinfunction "1_1") (pintype "passive"))
      (node (ref "C41") (pin "1") (pinfunction "1_1") (pintype "passive"))
      (node (ref "C42") (pin "2") (pinfunction "2_2") (pintype "passive"))
      (node (ref "C44") (pin "2") (pinfunction "2_2") (pintype "passive"))
      (node (ref "C45") (pin "2") (pinfunction "2_2") (pintype "passive"))
      (node (ref "C5") (pin "2") (pinfunction "2_2") (pintype "passive"))
      (node (ref "C6") (pin "2") (pinfunction "2_2") (pintype "passive"))
      (node (ref "C9") (pin "2") (pinfunction "2_2") (pintype "passive"))
      (node (ref "D3") (pin "1") (pinfunction "A_1") (pintype "passive"))
      (node (ref "IC1") (pin "1") (pinfunction "GND_1") (pintype "power_in"))
      (node (ref "IC2") (pin "1") (pinfunction "C_1") (pintype "passive"))
      (node (ref "IC3") (pin "10") (pinfunction "+IN_10") (pintype "input"))
      (node (ref "IC3") (pin "11") (pinfunction "V-_11") (pintype "power_in"))
      (node (ref "IC3") (pin "12") (pinfunction "+IN_12") (pintype "input"))
      (node (ref "IC3") (pin "3") (pinfunction "+IN_3") (pintype "input"))
      (node (ref "IC3") (pin "5") (pinfunction "+IN_5") (pintype "input"))
      (node (ref "IC4") (pin "12") (pinfunction "VSSA_12") (pintype "power_in"))
      (node (ref "IC4") (pin "18") (pinfunction "VSS_4_18") (pintype "power_in"))
      (node (ref "IC4") (pin "26") (pinfunction "PB0/ADC8/TIM3_CH3_26") (pintype "bidirectional"))
      (node (ref "IC4") (pin "28") (pinfunction "PB2/BOOT1_28") (pintype "bidirectional"))
      (node (ref "IC4") (pin "63") (pinfunction "VSS_3_63") (pintype "power_in"))
      (node (ref "IC5") (pin "11") (pinfunction "HPGND_11") (pintype "bidirectional"))
      (node (ref "IC5") (pin "15") (pinfunction "AGND_15") (pintype "bidirectional"))
      (node (ref "IC5") (pin "21") (pinfunction "MODE_21") (pintype "bidirectional"))
      (node (ref "IC5") (pin "22") (pinfunction "CSB_22") (pintype "bidirectional"))
      (node (ref "IC5") (pin "28") (pinfunction "DGND_28") (pintype "bidirectional"))
      (node (ref "IC6") (pin "3") (pinfunction "+IN_3") (pintype "input"))
      (node (ref "IC6") (pin "5") (pinfunction "+IN_5") (pintype "input"))
      (node (ref "J1") (pin "P1") (pinfunction "1_P1") (pintype "passive"))
      (node (ref "J2") (pin "P1") (pinfunction "1_P1") (pintype "passive"))
      (node (ref "J3") (pin "P1") (pinfunction "1_P1") (pintype "passive"))
      (node (ref "J4") (pin "P1") (pinfunction "1_P1") (pintype "passive"))
      (node (ref "J5") (pin "P1") (pinfunction "1_P1") (pintype "passive"))
      (node (ref "J6") (pin "P1") (pinfunction "1_P1") (pintype "passive"))
      (node (ref "J7") (pin "P1") (pinfunction "1_P1") (pintype "passive"))
      (node (ref "J8") (pin "P1") (pinfunction "1_P1") (pintype "passive"))
      (node (ref "JP1") (pin "3") (pinfunction "3_3") (pintype "passive"))
      (node (ref "JP1") (pin "5") (pinfunction "5_5") (pintype "passive"))
      (node (ref "JP1") (pin "9") (pinfunction "9_9") (pintype "passive"))
      (node (ref "JP2") (pin "1") (pinfunction "1_1") (pintype "passive"))
      (node (ref "JP3") (pin "3") (pinfunction "3_3") (pintype "passive"))
      (node (ref "JP3") (pin "4") (pinfunction "4_4") (pintype "passive"))
      (node (ref "JP3") (pin "5") (pinfunction "5_5") (pintype "passive"))
      (node (ref "JP3") (pin "6") (pinfunction "6_6") (pintype "passive"))
      (node (ref "JP3") (pin "7") (pinfunction "7_7") (pintype "passive"))
      (node (ref "JP3") (pin "8") (pinfunction "8_8") (pintype "passive"))
      (node (ref "LED1") (pin "GND") (pinfunction "C_GND") (pintype "bidirectional"))
      (node (ref "LED2") (pin "2") (pinfunction "C_2") (pintype "bidirectional"))
      (node (ref "R14") (pin "1") (pinfunction "1_1") (pintype "passive"))
      (node (ref "R23") (pin "P$3") (pinfunction "A_P$3") (pintype "passive"))
      (node (ref "R26") (pin "P$3") (pinfunction "A_P$3") (pintype "passive"))
      (node (ref "R27") (pin "P$3") (pinfunction "A_P$3") (pintype "passive"))
      (node (ref "R28") (pin "1") (pinfunction "1_1") (pintype "passive"))
      (node (ref "R33") (pin "1") (pinfunction "1_1") (pintype "passive"))
      (node (ref "R36") (pin "1") (pinfunction "1_1") (pintype "passive"))
      (node (ref "R39") (pin "1") (pinfunction "1_1") (pintype "passive"))
      (node (ref "R7") (pin "P$3") (pinfunction "A_P$3") (pintype "passive"))
      (node (ref "SW1") (pin "A") (pinfunction "P_A") (pintype "passive"))
      (node (ref "SW1") (pin "A'") (pinfunction "P1_A'") (pintype "passive"))
      (node (ref "SW3") (pin "1") (pinfunction "1_1") (pintype "passive"))
      (node (ref "SW3") (pin "2") (pinfunction "2_2") (pintype "passive"))
    )
    (net (code "9") (name "I2C_SCL") (class "Default")
      (node (ref "IC4") (pin "29") (pinfunction "PB10/SPI2_SCK/I2S_SCK/I2C2_SCL/USART3_TX_29") (pintype "bidirectional"))
      (node (ref "IC5") (pin "24") (pinfunction "SCLK_24") (pintype "bidirectional"))
      (node (ref "R24") (pin "1") (pinfunction "1_1") (pintype "passive"))
    )
    (net (code "10") (name "I2C_SDA") (class "Default")
      (node (ref "IC4") (pin "30") (pinfunction "PB11/I2C2_SDA/USART3_RX_30") (pintype "bidirectional"))
      (node (ref "IC5") (pin "23") (pinfunction "SDIN_23") (pintype "bidirectional"))
      (node (ref "R25") (pin "1") (pinfunction "1_1") (pintype "passive"))
    )
    (net (code "11") (name "I2S_LRCK") (class "Default")
      (node (ref "IC4") (pin "33") (pinfunction "PB12/SPI2_NSS/I2S2_WS/I2C2_SMBA/USART3_CK/TIM1_BKIN_33") (pintype "bidirectional"))
      (node (ref "IC5") (pin "5") (pinfunction "DACLRC_5") (pintype "bidirectional"))
      (node (ref "IC5") (pin "7") (pinfunction "ADCLRC_7") (pintype "bidirectional"))
    )
    (net (code "12") (name "I2S_SCK") (class "Default")
      (node (ref "IC4") (pin "34") (pinfunction "PB13/SPI2_SCK/I2S2_SCK/USART3_CTS/TIM1_CH1N_34") (pintype "bidirectional"))
      (node (ref "IC5") (pin "3") (pinfunction "BCLK_3") (pintype "bidirectional"))
    )
    (net (code "13") (name "I2S_SIN") (class "Default")
      (node (ref "IC4") (pin "35") (pinfunction "PB14/SPI2_MISO/USART3_RTS/TIM1_CH2N_35") (pintype "bidirectional"))
      (node (ref "IC5") (pin "6") (pinfunction "ADCDAT_6") (pintype "bidirectional"))
    )
    (net (code "14") (name "I2S_SOUT") (class "Default")
      (node (ref "IC4") (pin "36") (pinfunction "PB15/SPI2_MOSI/I2S2_SD/TIM1_CH3N_36") (pintype "bidirectional"))
      (node (ref "IC5") (pin "4") (pinfunction "DACDAT_4") (pintype "bidirectional"))
    )
    (net (code "15") (name "IN_1") (class "Default")
      (node (ref "C37") (pin "+") (pinfunction "+_+") (pintype "passive"))
      (node (ref "IC5") (pin "20") (pinfunction "LLINEIN_20") (pintype "bidirectional"))
    )
    (net (code "16") (name "IN_2") (class "Default")
      (node (ref "C43") (pin "+") (pinfunction "+_+") (pintype "passive"))
      (node (ref "IC5") (pin "19") (pinfunction "RLINEIN_19") (pintype "bidirectional"))
    )
    (net (code "17") (name "JTCK") (class "Default")
      (node (ref "IC4") (pin "49") (pinfunction "PA14/JTCK-SWCLK_49") (pintype "bidirectional"))
      (node (ref "JP1") (pin "4") (pinfunction "4_4") (pintype "passive"))
    )
    (net (code "18") (name "JTDI") (class "Default")
      (node (ref "IC4") (pin "50") (pinfunction "PA15/JTDI/SPI3_NSS/I2S3_WS_50") (pintype "bidirectional"))
      (node (ref "JP1") (pin "8") (pinfunction "8_8") (pintype "passive"))
    )
    (net (code "19") (name "JTDO") (class "Default")
      (node (ref "IC4") (pin "55") (pinfunction "PB3/JTDO/SPI3_SCK/I2S3_SCK_55") (pintype "bidirectional"))
      (node (ref "JP1") (pin "6") (pinfunction "6_6") (pintype "passive"))
    )
    (net (code "20") (name "JTMS") (class "Default")
      (node (ref "IC4") (pin "46") (pinfunction "PA13/JTMS-SWDAT_46") (pintype "bidirectional"))
      (node (ref "JP1") (pin "2") (pinfunction "2_2") (pintype "passive"))
    )
    (net (code "21") (name "LED_B") (class "Default")
      (node (ref "IC4") (pin "59") (pinfunction "PB7/I2C1_SDA/TIM4_CH2/USART1_RX_59") (pintype "bidirectional"))
      (node (ref "R4") (pin "1") (pinfunction "1_1") (pintype "passive"))
    )
    (net (code "22") (name "LED_CARRIER_G") (class "Default")
      (node (ref "IC4") (pin "25") (pinfunction "PC5/ADC15_25") (pintype "bidirectional"))
      (node (ref "R22") (pin "1") (pinfunction "1_1") (pintype "passive"))
    )
    (net (code "23") (name "LED_CARRIER_R") (class "Default")
      (node (ref "IC4") (pin "24") (pinfunction "PC4/ADC14_24") (pintype "bidirectional"))
      (node (ref "R21") (pin "1") (pinfunction "1_1") (pintype "passive"))
    )
    (net (code "24") (name "LED_G") (class "Default")
      (node (ref "IC4") (pin "58") (pinfunction "PB6/I2C1_SCL/TIM4_CH1/USART1_TX_58") (pintype "bidirectional"))
      (node (ref "R5") (pin "1") (pinfunction "1_1") (pintype "passive"))
    )
    (net (code "25") (name "LED_R") (class "Default")
      (node (ref "IC4") (pin "61") (pinfunction "PB8/TIM4_CH3/I2C1_SCL_61") (pintype "bidirectional"))
      (node (ref "R3") (pin "1") (pinfunction "1_1") (pintype "passive"))
    )
    (net (code "26") (name "LEVEL_1_CV") (class "Default")
      (node (ref "C8") (pin "2") (pinfunction "2_2") (pintype "passive"))
      (node (ref "IC3") (pin "8") (pinfunction "OUT_8") (pintype "output"))
      (node (ref "IC4") (pin "15") (pinfunction "PA1/USART2_RTS/UART4_RX/ADC1/TIM2_CH2_15") (pintype "bidirectional"))
      (node (ref "R13") (pin "1") (pinfunction "1_1") (pintype "passive"))
    )
    (net (code "27") (name "LEVEL_1_POT") (class "Default")
      (node (ref "C33") (pin "1") (pinfunction "1_1") (pintype "passive"))
      (node (ref "IC4") (pin "21") (pinfunction "PA5/SPI1_SCK/ADC5/DAC2_21") (pintype "bidirectional"))
      (node (ref "R26") (pin "P$2") (pinfunction "S_P$2") (pintype "passive"))
    )
    (net (code "28") (name "LEVEL_2_CV") (class "Default")
      (node (ref "C7") (pin "2") (pinfunction "2_2") (pintype "passive"))
      (node (ref "IC3") (pin "14") (pinfunction "OUT_14") (pintype "output"))
      (node (ref "IC4") (pin "16") (pinfunction "PA2/USART2_TX/ADC2/TIM2_CH3_16") (pintype "bidirectional"))
      (node (ref "R12") (pin "1") (pinfunction "1_1") (pintype "passive"))
    )
    (net (code "29") (name "LEVEL_2_POT") (class "Default")
      (node (ref "C31") (pin "1") (pinfunction "1_1") (pintype "passive"))
      (node (ref "IC4") (pin "22") (pinfunction "PA6/SPI1_MISO/ADC6/TIM3_CH1_22") (pintype "bidirectional"))
      (node (ref "R27") (pin "P$2") (pinfunction "S_P$2") (pintype "passive"))
    )
    (net (code "30") (name "MOD_OUT") (class "Default")
      (node (ref "C32") (pin "+") (pinfunction "+_+") (pintype "passive"))
      (node (ref "IC5") (pin "12") (pinfunction "LOUT_12") (pintype "bidirectional"))
    )
    (net (code "31") (name "NORMALIZATION_PROBE") (class "Default")
      (node (ref "D3") (pin "3") (pinfunction "AC_3") (pintype "passive"))
      (node (ref "IC4") (pin "39") (pinfunction "PC8_39") (pintype "bidirectional"))
      (node (ref "R32") (pin "1") (pinfunction "1_1") (pintype "passive"))
      (node (ref "R35") (pin "1") (pinfunction "1_1") (pintype "passive"))
      (node (ref "R40") (pin "2") (pinfunction "2_2") (pintype "passive"))
      (node (ref "R41") (pin "2") (pinfunction "2_2") (pintype "passive"))
    )
    (net (code "32") (name "Net-(C32-Pad-)") (class "Default")
      (node (ref "C32") (pin "-") (pinfunction "-_-") (pintype "passive"))
      (node (ref "R28") (pin "2") (pinfunction "2_2") (pintype "passive"))
      (node (ref "R29") (pin "2") (pinfunction "2_2") (pintype "passive"))
    )
    (net (code "33") (name "Net-(C37-Pad-)") (class "Default")
      (node (ref "C37") (pin "-") (pinfunction "-_-") (pintype "passive"))
      (node (ref "C44") (pin "1") (pinfunction "1_1") (pintype "passive"))
      (node (ref "R36") (pin "2") (pinfunction "2_2") (pintype "passive"))
      (node (ref "R37") (pin "1") (pinfunction "1_1") (pintype "passive"))
    )
    (net (code "34") (name "Net-(C39-Pad-)") (class "Default")
      (node (ref "C39") (pin "-") (pinfunction "-_-") (pintype "passive"))
      (node (ref "R33") (pin "2") (pinfunction "2_2") (pintype "passive"))
      (node (ref "R34") (pin "2") (pinfunction "2_2") (pintype "passive"))
    )
    (net (code "35") (name "Net-(C43-Pad-)") (class "Default")
      (node (ref "C43") (pin "-") (pinfunction "-_-") (pintype "passive"))
      (node (ref "C45") (pin "1") (pinfunction "1_1") (pintype "passive"))
      (node (ref "R38") (pin "1") (pinfunction "1_1") (pintype "passive"))
      (node (ref "R39") (pin "2") (pinfunction "2_2") (pintype "passive"))
    )
    (net (code "36") (name "Net-(D1-PadA)") (class "Default")
      (node (ref "D1") (pin "A") (pinfunction "A_A") (pintype "passive"))
      (node (ref "JP3") (pin "1") (pinfunction "1_1") (pintype "passive"))
      (node (ref "JP3") (pin "2") (pinfunction "2_2") (pintype "passive"))
    )
    (net (code "37") (name "Net-(D1-PadC)") (class "Default")
      (node (ref "D1") (pin "C") (pinfunction "C_C") (pintype "passive"))
      (node (ref "L1") (pin "2") (pinfunction "2_2") (pintype "passive"))
    )
    (net (code "38") (name "Net-(D2-PadA)") (class "Default")
      (node (ref "D2") (pin "A") (pinfunction "A_A") (pintype "passive"))
      (node (ref "L3") (pin "2") (pinfunction "2_2") (pintype "passive"))
    )
    (net (code "39") (name "Net-(D2-PadC)") (class "Default")
      (node (ref "D2") (pin "C") (pinfunction "C_C") (pintype "passive"))
      (node (ref "JP3") (pin "10") (pinfunction "10_10") (pintype "passive"))
      (node (ref "JP3") (pin "9") (pinfunction "9_9") (pintype "passive"))
    )
    (net (code "40") (name "Net-(IC1-VIN)") (class "Default")
      (node (ref "C2") (pin "+") (pinfunction "+_+") (pintype "passive"))
      (node (ref "IC1") (pin "2") (pinfunction "VIN_2") (pintype "input"))
      (node (ref "R1") (pin "1") (pinfunction "1_1") (pintype "passive"))
    )
    (net (code "41") (name "Net-(IC3A--IN)") (class "Default")
      (node (ref "C12") (pin "1") (pinfunction "1_1") (pintype "passive"))
      (node (ref "IC3") (pin "2") (pinfunction "-IN_2") (pintype "input"))
      (node (ref "R15") (pin "2") (pinfunction "2_2") (pintype "passive"))
      (node (ref "R17") (pin "1") (pinfunction "1_1") (pintype "passive"))
      (node (ref "R19") (pin "1") (pinfunction "1_1") (pintype "passive"))
    )
    (net (code "42") (name "Net-(IC3B--IN)") (class "Default")
      (node (ref "C14") (pin "1") (pinfunction "1_1") (pintype "passive"))
      (node (ref "IC3") (pin "6") (pinfunction "-IN_6") (pintype "input"))
      (node (ref "R16") (pin "2") (pinfunction "2_2") (pintype "passive"))
      (node (ref "R18") (pin "1") (pinfunction "1_1") (pintype "passive"))
      (node (ref "R20") (pin "1") (pinfunction "1_1") (pintype "passive"))
    )
    (net (code "43") (name "Net-(IC3C--IN)") (class "Default")
      (node (ref "C8") (pin "1") (pinfunction "1_1") (pintype "passive"))
      (node (ref "IC3") (pin "9") (pinfunction "-IN_9") (pintype "input"))
      (node (ref "R11") (pin "1") (pinfunction "1_1") (pintype "passive"))
      (node (ref "R13") (pin "2") (pinfunction "2_2") (pintype "passive"))
      (node (ref "R9") (pin "1") (pinfunction "1_1") (pintype "passive"))
    )
    (net (code "44") (name "Net-(IC3D--IN)") (class "Default")
      (node (ref "C7") (pin "1") (pinfunction "1_1") (pintype "passive"))
      (node (ref "IC3") (pin "13") (pinfunction "-IN_13") (pintype "input"))
      (node (ref "R10") (pin "1") (pinfunction "1_1") (pintype "passive"))
      (node (ref "R12") (pin "2") (pinfunction "2_2") (pintype "passive"))
      (node (ref "R8") (pin "1") (pinfunction "1_1") (pintype "passive"))
    )
    (net (code "45") (name "Net-(IC4-PB4{slash}NJTRST{slash}SPI3_MISO{slash}SPI1_MISO)") (class "Default")
      (node (ref "IC4") (pin "56") (pinfunction "PB4/NJTRST/SPI3_MISO/SPI1_MISO_56") (pintype "bidirectional"))
      (node (ref "TP3") (pin "P$1") (pinfunction "1_P$1") (pintype "bidirectional"))
    )
    (net (code "46") (name "Net-(IC4-PB5{slash}I2C1_SMBA{slash}SPI1_MOSI{slash}SPI3_MOSI{slash}I2S3_SD)") (class "Default")
      (node (ref "IC4") (pin "57") (pinfunction "PB5/I2C1_SMBA/SPI1_MOSI/SPI3_MOSI/I2S3_SD_57") (pintype "bidirectional"))
      (node (ref "TP2") (pin "P$1") (pinfunction "1_P$1") (pintype "bidirectional"))
    )
    (net (code "47") (name "Net-(IC4-PB9{slash}SPI2_NSS{slash}I2S2_WS{slash}I2C1_SDA{slash}TIM4_CH4)") (class "Default")
      (node (ref "IC4") (pin "62") (pinfunction "PB9/SPI2_NSS/I2S2_WS/I2C1_SDA/TIM4_CH4_62") (pintype "bidirectional"))
      (node (ref "TP1") (pin "P$1") (pinfunction "1_P$1") (pintype "bidirectional"))
    )
    (net (code "48") (name "Net-(IC4-PC11{slash}UART4_RX{slash}SPI3_MISO{slash}USART3_RX)") (class "Default")
      (node (ref "IC4") (pin "52") (pinfunction "PC11/UART4_RX/SPI3_MISO/USART3_RX_52") (pintype "bidirectional"))
      (node (ref "TP4") (pin "P$1") (pinfunction "1_P$1") (pintype "bidirectional"))
    )
    (net (code "49") (name "Net-(IC4-PD0{slash}OSC_IN)") (class "Default")
      (node (ref "C11") (pin "2") (pinfunction "2_2") (pintype "passive"))
      (node (ref "IC4") (pin "5") (pinfunction "PD0/OSC_IN_5") (pintype "bidirectional"))
      (node (ref "Q1") (pin "2") (pinfunction "2_2") (pintype "passive"))
    )
    (net (code "50") (name "Net-(IC4-PD1{slash}OSC_OUT)") (class "Default")
      (node (ref "C10") (pin "2") (pinfunction "2_2") (pintype "passive"))
      (node (ref "IC4") (pin "6") (pinfunction "PD1/OSC_OUT_6") (pintype "bidirectional"))
      (node (ref "Q1") (pin "1") (pinfunction "1_1") (pintype "passive"))
    )
    (net (code "51") (name "Net-(IC4-VCAP_1)") (class "Default")
      (node (ref "C19") (pin "1") (pinfunction "1_1") (pintype "passive"))
      (node (ref "IC4") (pin "31") (pinfunction "VCAP_1_31") (pintype "power_in"))
    )
    (net (code "52") (name "Net-(IC4-VCAP_2)") (class "Default")
      (node (ref "C22") (pin "1") (pinfunction "1_1") (pintype "passive"))
      (node (ref "IC4") (pin "47") (pinfunction "VCAP_2_47") (pintype "power_in"))
    )
    (net (code "53") (name "Net-(IC5-VMID)") (class "Default")
      (node (ref "C36") (pin "+") (pinfunction "+_+") (pintype "passive"))
      (node (ref "C42") (pin "1") (pinfunction "1_1") (pintype "passive"))
      (node (ref "IC5") (pin "16") (pinfunction "VMID_16") (pintype "bidirectional"))
    )
    (net (code "54") (name "Net-(IC5-XTI{slash}MCLK)") (class "Default")
      (node (ref "C41") (pin "2") (pinfunction "2_2") (pintype "passive"))
      (node (ref "IC5") (pin "25") (pinfunction "XTI/MCLK_25") (pintype "bidirectional"))
      (node (ref "Q2") (pin "2") (pinfunction "2_2") (pintype "passive"))
    )
    (net (code "55") (name "Net-(IC5-XTO)") (class "Default")
      (node (ref "C26") (pin "2") (pinfunction "2_2") (pintype "passive"))
      (node (ref "IC5") (pin "26") (pinfunction "XTO_26") (pintype "bidirectional"))
      (node (ref "Q2") (pin "1") (pinfunction "1_1") (pintype "passive"))
    )
    (net (code "56") (name "Net-(IC6A--IN)") (class "Default")
      (node (ref "C35") (pin "1") (pinfunction "1_1") (pintype "passive"))
      (node (ref "IC6") (pin "2") (pinfunction "-IN_2") (pintype "input"))
      (node (ref "R29") (pin "1") (pinfunction "1_1") (pintype "passive"))
      (node (ref "R30") (pin "2") (pinfunction "2_2") (pintype "passive"))
    )
    (net (code "57") (name "Net-(IC6A-OUT)") (class "Default")
      (node (ref "C35") (pin "2") (pinfunction "2_2") (pintype "passive"))
      (node (ref "IC6") (pin "1") (pinfunction "OUT_1") (pintype "output"))
      (node (ref "R30") (pin "1") (pinfunction "1_1") (pintype "passive"))
      (node (ref "R42") (pin "2") (pinfunction "2_2") (pintype "passive"))
    )
    (net (code "58") (name "Net-(IC6B--IN)") (class "Default")
      (node (ref "C38") (pin "1") (pinfunction "1_1") (pintype "passive"))
      (node (ref "IC6") (pin "6") (pinfunction "-IN_6") (pintype "input"))
      (node (ref "R31") (pin "2") (pinfunction "2_2") (pintype "passive"))
      (node (ref "R34") (pin "1") (pinfunction "1_1") (pintype "passive"))
    )
    (net (code "59") (name "Net-(IC6B-OUT)") (class "Default")
      (node (ref "C38") (pin "2") (pinfunction "2_2") (pintype "passive"))
      (node (ref "IC6") (pin "7") (pinfunction "OUT_7") (pintype "output"))
      (node (ref "R31") (pin "1") (pinfunction "1_1") (pintype "passive"))
      (node (ref "R43") (pin "2") (pinfunction "2_2") (pintype "passive"))
    )
    (net (code "60") (name "Net-(J1-2)") (class "Default")
      (node (ref "J1") (pin "P2") (pinfunction "2_P2") (pintype "passive"))
      (node (ref "R32") (pin "2") (pinfunction "2_2") (pintype "passive"))
    )
    (net (code "61") (name "Net-(J1-3)") (class "Default")
      (node (ref "J1") (pin "P3") (pinfunction "3_P3") (pintype "passive"))
      (node (ref "R9") (pin "2") (pinfunction "2_2") (pintype "passive"))
    )
    (net (code "62") (name "Net-(J2-2)") (class "Default")
      (node (ref "J2") (pin "P2") (pinfunction "2_P2") (pintype "passive"))
      (node (ref "R35") (pin "2") (pinfunction "2_2") (pintype "passive"))
    )
    (net (code "63") (name "Net-(J2-3)") (class "Default")
      (node (ref "J2") (pin "P3") (pinfunction "3_P3") (pintype "passive"))
      (node (ref "R8") (pin "2") (pinfunction "2_2") (pintype "passive"))
    )
    (net (code "64") (name "Net-(J3-3)") (class "Default")
      (node (ref "J3") (pin "P3") (pinfunction "3_P3") (pintype "passive"))
      (node (ref "R17") (pin "2") (pinfunction "2_2") (pintype "passive"))
    )
    (net (code "65") (name "Net-(J4-3)") (class "Default")
      (node (ref "J4") (pin "P3") (pinfunction "3_P3") (pintype "passive"))
      (node (ref "R18") (pin "2") (pinfunction "2_2") (pintype "passive"))
    )
    (net (code "66") (name "Net-(J5-2)") (class "Default")
      (node (ref "J5") (pin "P2") (pinfunction "2_P2") (pintype "passive"))
      (node (ref "R40") (pin "1") (pinfunction "1_1") (pintype "passive"))
    )
    (net (code "67") (name "Net-(J5-3)") (class "Default")
      (node (ref "J5") (pin "P3") (pinfunction "3_P3") (pintype "passive"))
      (node (ref "R37") (pin "2") (pinfunction "2_2") (pintype "passive"))
    )
    (net (code "68") (name "Net-(J6-2)") (class "Default")
      (node (ref "J6") (pin "P2") (pinfunction "2_P2") (pintype "passive"))
      (node (ref "R41") (pin "1") (pinfunction "1_1") (pintype "passive"))
    )
    (net (code "69") (name "Net-(J6-3)") (class "Default")
      (node (ref "J6") (pin "P3") (pinfunction "3_P3") (pintype "passive"))
      (node (ref "R38") (pin "2") (pinfunction "2_2") (pintype "passive"))
    )
    (net (code "70") (name "Net-(J7-3)") (class "Default")
      (node (ref "J7") (pin "P3") (pinfunction "3_P3") (pintype "passive"))
      (node (ref "R42") (pin "1") (pinfunction "1_1") (pintype "passive"))
    )
    (net (code "71") (name "Net-(J8-3)") (class "Default")
      (node (ref "J8") (pin "P3") (pinfunction "3_P3") (pintype "passive"))
      (node (ref "R43") (pin "1") (pinfunction "1_1") (pintype "passive"))
    )
    (net (code "72") (name "Net-(LED1-PadBLU)") (class "Default")
      (node (ref "LED1") (pin "BLU") (pinfunction "BLU_BLU") (pintype "bidirectional"))
      (node (ref "R4") (pin "2") (pinfunction "2_2") (pintype "passive"))
    )
    (net (code "73") (name "Net-(LED1-PadGRN)") (class "Default")
      (node (ref "LED1") (pin "GRN") (pinfunction "GRN_GRN") (pintype "bidirectional"))
      (node (ref "R5") (pin "2") (pinfunction "2_2") (pintype "passive"))
    )
    (net (code "74") (name "Net-(LED1-PadRED)") (class "Default")
      (node (ref "LED1") (pin "RED") (pinfunction "RED_RED") (pintype "bidirectional"))
      (node (ref "R3") (pin "2") (pinfunction "2_2") (pintype "passive"))
    )
    (net (code "75") (name "Net-(LED2-GRN)") (class "Default")
      (node (ref "LED2") (pin "1") (pinfunction "GRN_1") (pintype "bidirectional"))
      (node (ref "R22") (pin "2") (pinfunction "2_2") (pintype "passive"))
    )
    (net (code "76") (name "Net-(LED2-RED)") (class "Default")
      (node (ref "LED2") (pin "3") (pinfunction "RED_3") (pintype "bidirectional"))
      (node (ref "R21") (pin "2") (pinfunction "2_2") (pintype "passive"))
    )
    (net (code "77") (name "PARAMETER_CV") (class "Default")
      (node (ref "C14") (pin "2") (pinfunction "2_2") (pintype "passive"))
      (node (ref "IC3") (pin "7") (pinfunction "OUT_7") (pintype "output"))
      (node (ref "IC4") (pin "17") (pinfunction "PA3/USART2_RX/ADC3/TIM2_CH4_17") (pintype "bidirectional"))
      (node (ref "R16") (pin "1") (pinfunction "1_1") (pintype "passive"))
    )
    (net (code "78") (name "PARAMETER_POT") (class "Default")
      (node (ref "C25") (pin "1") (pinfunction "1_1") (pintype "passive"))
      (node (ref "IC4") (pin "23") (pinfunction "PA7/SPI1_MOSI/ADC7/TIM3_CH2_23") (pintype "bidirectional"))
      (node (ref "R23") (pin "P$2") (pinfunction "S_P$2") (pintype "passive"))
    )
    (net (code "79") (name "RESET") (class "Default")
      (node (ref "IC4") (pin "7") (pinfunction "NRST_7") (pintype "bidirectional"))
      (node (ref "JP1") (pin "10") (pinfunction "10_10") (pintype "passive"))
      (node (ref "R2") (pin "1") (pinfunction "1_1") (pintype "passive"))
      (node (ref "SW1") (pin "B") (pinfunction "S_B") (pintype "passive"))
      (node (ref "SW1") (pin "B'") (pinfunction "S1_B'") (pintype "passive"))
    )
    (net (code "80") (name "RX") (class "Default")
      (node (ref "IC4") (pin "43") (pinfunction "PA10/USART1_RX/TIM1_CH3_43") (pintype "bidirectional"))
      (node (ref "JP2") (pin "4") (pinfunction "4_4") (pintype "passive"))
    )
    (net (code "81") (name "SW_CARRIER") (class "Default")
      (node (ref "IC4") (pin "27") (pinfunction "PB1/ADC9/TIM3_CH4_27") (pintype "bidirectional"))
      (node (ref "SW3") (pin "3") (pinfunction "3_3") (pintype "passive"))
      (node (ref "SW3") (pin "4") (pinfunction "4_4") (pintype "passive"))
    )
    (net (code "82") (name "TX") (class "Default")
      (node (ref "IC4") (pin "42") (pinfunction "PA9/USART1_TX/TIM1_CH2_42") (pintype "bidirectional"))
      (node (ref "JP2") (pin "5") (pinfunction "5_5") (pintype "passive"))
    )
    (net (code "83") (name "VBAT") (class "Default")
      (node (ref "IC4") (pin "1") (pinfunction "VBAT_1") (pintype "power_in"))
    )
    (net (code "84") (name "VCC") (class "Default")
      (node (ref "C1") (pin "+") (pinfunction "+_+") (pintype "passive"))
      (node (ref "C34") (pin "1") (pinfunction "1_1") (pintype "passive"))
      (node (ref "IC6") (pin "8") (pinfunction "V+_8") (pintype "power_in"))
      (node (ref "L1") (pin "1") (pinfunction "1_1") (pintype "passive"))
      (node (ref "R1") (pin "2") (pinfunction "2_2") (pintype "passive"))
    )
    (net (code "85") (name "VEE") (class "Default")
      (node (ref "C3") (pin "-") (pinfunction "-_-") (pintype "passive"))
      (node (ref "C40") (pin "2") (pinfunction "2_2") (pintype "passive"))
      (node (ref "IC6") (pin "4") (pinfunction "V-_4") (pintype "power_in"))
      (node (ref "L3") (pin "1") (pinfunction "1_1") (pintype "passive"))
      (node (ref "R6") (pin "1") (pinfunction "1_1") (pintype "passive"))
    )
    (net (code "86") (name "unconnected-(IC4-PA8{slash}USART1_CK{slash}TIM1_CH1{slash}MCO-Pad41)") (class "Default")
      (node (ref "IC4") (pin "41") (pinfunction "PA8/USART1_CK/TIM1_CH1/MCO_41") (pintype "bidirectional"))
    )
    (net (code "87") (name "unconnected-(IC4-PA11{slash}USART1_CTS{slash}CANRX{slash}USBDM{slash}TIM1_CH4-Pad44)") (class "Default")
      (node (ref "IC4") (pin "44") (pinfunction "PA11/USART1_CTS/CANRX/USBDM/TIM1_CH4_44") (pintype "bidirectional"))
    )
    (net (code "88") (name "unconnected-(IC4-PA12{slash}USART1_RTS{slash}CANTX{slash}USBDP{slash}TIM1_ETR-Pad45)") (class "Default")
      (node (ref "IC4") (pin "45") (pinfunction "PA12/USART1_RTS/CANTX/USBDP/TIM1_ETR_45") (pintype "bidirectional"))
    )
    (net (code "89") (name "unconnected-(IC4-PC0{slash}ADC10-Pad8)") (class "Default")
      (node (ref "IC4") (pin "8") (pinfunction "PC0/ADC10_8") (pintype "bidirectional"))
    )
    (net (code "90") (name "unconnected-(IC4-PC1{slash}ADC11-Pad9)") (class "Default")
      (node (ref "IC4") (pin "9") (pinfunction "PC1/ADC11_9") (pintype "bidirectional"))
    )
    (net (code "91") (name "unconnected-(IC4-PC2{slash}SPI2_MISO{slash}ADC12-Pad10)") (class "Default")
      (node (ref "IC4") (pin "10") (pinfunction "PC2/SPI2_MISO/ADC12_10") (pintype "bidirectional"))
    )
    (net (code "92") (name "unconnected-(IC4-PC3{slash}SPI2_MOSI{slash}I2S2_SD{slash}ADC13-Pad11)") (class "Default")
      (node (ref "IC4") (pin "11") (pinfunction "PC3/SPI2_MOSI/I2S2_SD/ADC13_11") (pintype "bidirectional"))
    )
    (net (code "93") (name "unconnected-(IC4-PC6{slash}I2S2_MCK-Pad37)") (class "Default")
      (node (ref "IC4") (pin "37") (pinfunction "PC6/I2S2_MCK_37") (pintype "bidirectional"))
    )
    (net (code "94") (name "unconnected-(IC4-PC7{slash}I2S3_MCK-Pad38)") (class "Default")
      (node (ref "IC4") (pin "38") (pinfunction "PC7/I2S3_MCK_38") (pintype "bidirectional"))
    )
    (net (code "95") (name "unconnected-(IC4-PC9{slash}I2S2_CKIN{slash}I2S3_CKIN-Pad40)") (class "Default")
      (node (ref "IC4") (pin "40") (pinfunction "PC9/I2S2_CKIN/I2S3_CKIN_40") (pintype "bidirectional"))
    )
    (net (code "96") (name "unconnected-(IC4-PC10{slash}SPI3_SCK{slash}I2S3_SCK{slash}UART4_TX-Pad51)") (class "Default")
      (node (ref "IC4") (pin "51") (pinfunction "PC10/SPI3_SCK/I2S3_SCK/UART4_TX_51") (pintype "bidirectional"))
    )
    (net (code "97") (name "unconnected-(IC4-PC12{slash}UART5_TX{slash}I2S3_SD{slash}USART3_CK-Pad53)") (class "Default")
      (node (ref "IC4") (pin "53") (pinfunction "PC12/UART5_TX/I2S3_SD/USART3_CK_53") (pintype "bidirectional"))
    )
    (net (code "98") (name "unconnected-(IC4-PC13-TAMPER-RTC-Pad2)") (class "Default")
      (node (ref "IC4") (pin "2") (pinfunction "PC13-TAMPER-RTC_2") (pintype "bidirectional"))
    )
    (net (code "99") (name "unconnected-(IC4-PC14{slash}OSC32_IN-Pad3)") (class "Default")
      (node (ref "IC4") (pin "3") (pinfunction "PC14/OSC32_IN_3") (pintype "bidirectional"))
    )
    (net (code "100") (name "unconnected-(IC4-PC15{slash}OSC_OUT-Pad4)") (class "Default")
      (node (ref "IC4") (pin "4") (pinfunction "PC15/OSC_OUT_4") (pintype "bidirectional"))
    )
    (net (code "101") (name "unconnected-(IC4-PD2{slash}TIM3-ETR-Pad54)") (class "Default")
      (node (ref "IC4") (pin "54") (pinfunction "PD2/TIM3-ETR_54") (pintype "bidirectional"))
    )
    (net (code "102") (name "unconnected-(IC5-CLKOUT-Pad2)") (class "Default")
      (node (ref "IC5") (pin "2") (pinfunction "CLKOUT_2") (pintype "bidirectional"))
    )
    (net (code "103") (name "unconnected-(IC5-LHPOUT-Pad9)") (class "Default")
      (node (ref "IC5") (pin "9") (pinfunction "LHPOUT_9") (pintype "bidirectional"))
    )
    (net (code "104") (name "unconnected-(IC5-MICBIAS-Pad17)") (class "Default")
      (node (ref "IC5") (pin "17") (pinfunction "MICBIAS_17") (pintype "bidirectional"))
    )
    (net (code "105") (name "unconnected-(IC5-MICIN-Pad18)") (class "Default")
      (node (ref "IC5") (pin "18") (pinfunction "MICIN_18") (pintype "bidirectional"))
    )
    (net (code "106") (name "unconnected-(IC5-RHPOUT-Pad10)") (class "Default")
      (node (ref "IC5") (pin "10") (pinfunction "RHPOUT_10") (pintype "bidirectional"))
    )
    (net (code "107") (name "unconnected-(J3-2-PadP2)") (class "Default")
      (node (ref "J3") (pin "P2") (pinfunction "2_P2") (pintype "passive"))
    )
    (net (code "108") (name "unconnected-(J4-2-PadP2)") (class "Default")
      (node (ref "J4") (pin "P2") (pinfunction "2_P2") (pintype "passive"))
    )
    (net (code "109") (name "unconnected-(J7-2-PadP2)") (class "Default")
      (node (ref "J7") (pin "P2") (pinfunction "2_P2") (pintype "passive"))
    )
    (net (code "110") (name "unconnected-(J8-2-PadP2)") (class "Default")
      (node (ref "J8") (pin "P2") (pinfunction "2_P2") (pintype "passive"))
    )
    (net (code "111") (name "unconnected-(JP1-Pad7)") (class "Default")
      (node (ref "JP1") (pin "7") (pinfunction "7_7") (pintype "passive"))
    )
    (net (code "112") (name "unconnected-(JP2-Pad2)") (class "Default")
      (node (ref "JP2") (pin "2") (pinfunction "2_2") (pintype "passive"))
    )
    (net (code "113") (name "unconnected-(JP2-Pad3)") (class "Default")
      (node (ref "JP2") (pin "3") (pinfunction "3_3") (pintype "passive"))
    )
    (net (code "114") (name "unconnected-(JP2-Pad6)") (class "Default")
      (node (ref "JP2") (pin "6") (pinfunction "6_6") (pintype "passive"))
    )
  )
)
